# power-rail.net
KiCad netlist of a schematic drawn in EAGLE
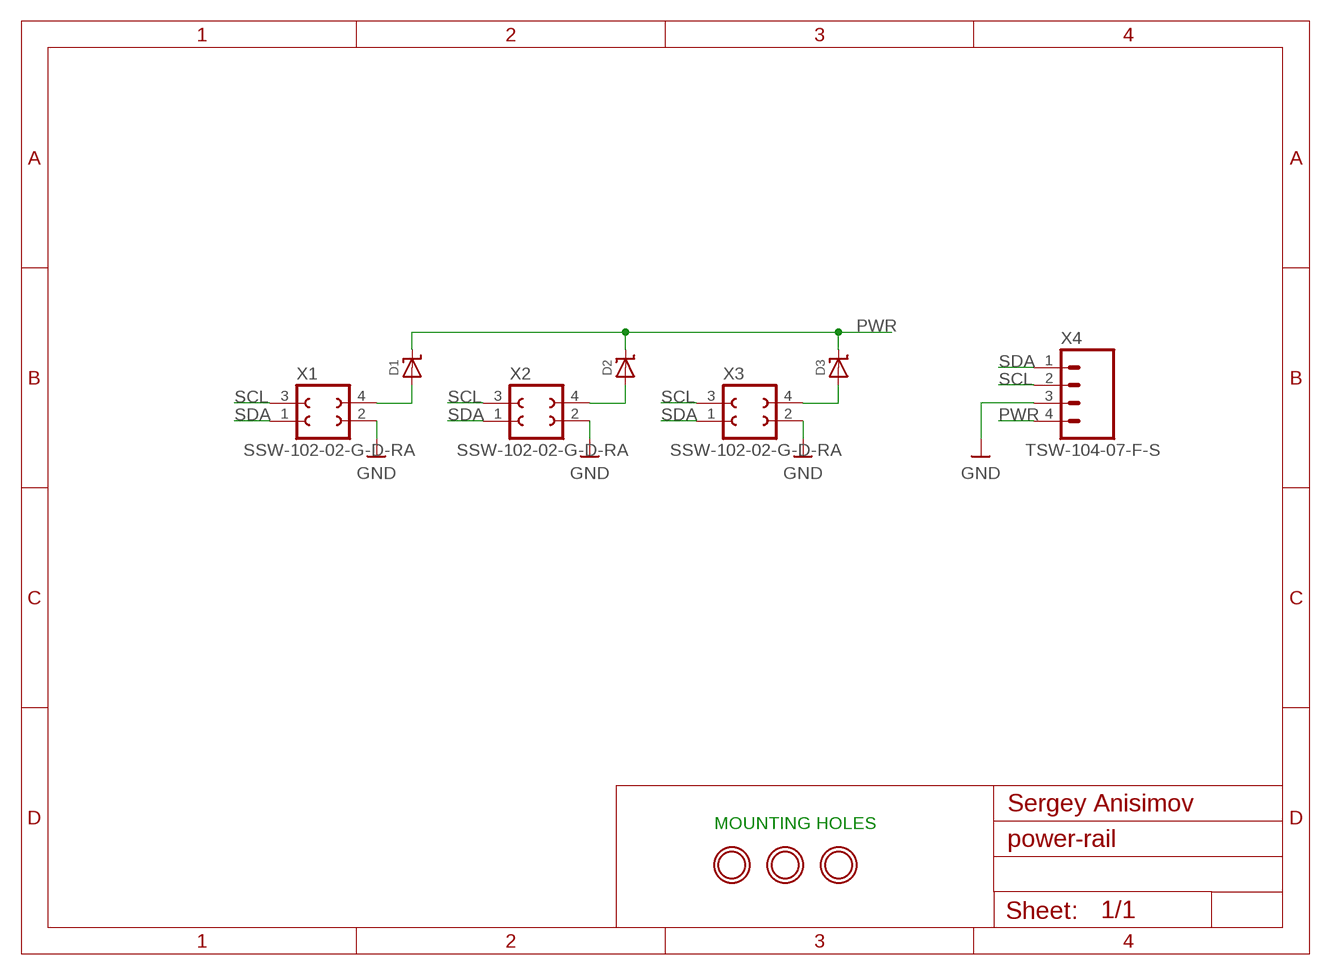
[diagram p0: schematic, sheet 1]

(export (version "E")
  (design (tool "Eeschema 10.0.6"))
  (components
    (comp (ref "D1")
      (value "DIODE-SCHOTTKYSOD−123FL")
      (footprint "eagle-import:SODFL3616X98")
      (libsource (lib "eagle-import") (part "DIODE-SCHOTTKYSOD−123FL"))
    )
    (comp (ref "D2")
      (value "DIODE-SCHOTTKYSOD−123FL")
      (footprint "eagle-import:SODFL3616X98")
      (libsource (lib "eagle-import") (part "DIODE-SCHOTTKYSOD−123FL"))
    )
    (comp (ref "D3")
      (value "DIODE-SCHOTTKYSOD−123FL")
      (footprint "eagle-import:SODFL3616X98")
      (libsource (lib "eagle-import") (part "DIODE-SCHOTTKYSOD−123FL"))
    )
    (comp (ref "U$5")
      (value "MOUNTING-HOLE2.7_THICK")
      (footprint "eagle-import:MOUNTINGHOLE_2.7_PLATED_THICK")
      (libsource (lib "eagle-import") (part "MOUNTING-HOLE2.7_THICK"))
    )
    (comp (ref "U$6")
      (value "MOUNTING-HOLE2.7_THICK")
      (footprint "eagle-import:MOUNTINGHOLE_2.7_PLATED_THICK")
      (libsource (lib "eagle-import") (part "MOUNTING-HOLE2.7_THICK"))
    )
    (comp (ref "U$7")
      (value "MOUNTING-HOLE2.7_THICK")
      (footprint "eagle-import:MOUNTINGHOLE_2.7_PLATED_THICK")
      (libsource (lib "eagle-import") (part "MOUNTING-HOLE2.7_THICK"))
    )
    (comp (ref "X1")
      (value "SSW-102-02-G-D-RA")
      (footprint "eagle-import:SSQ-102-02-T-D-RA")
      (libsource (lib "eagle-import") (part "CON-FE-02-02SSQ-102-02-T-D-RA"))
    )
    (comp (ref "X2")
      (value "SSW-102-02-G-D-RA")
      (footprint "eagle-import:SSQ-102-02-T-D-RA")
      (libsource (lib "eagle-import") (part "CON-FE-02-02SSQ-102-02-T-D-RA"))
    )
    (comp (ref "X3")
      (value "SSW-102-02-G-D-RA")
      (footprint "eagle-import:SSQ-102-02-T-D-RA")
      (libsource (lib "eagle-import") (part "CON-FE-02-02SSQ-102-02-T-D-RA"))
    )
    (comp (ref "X4")
      (value "TSW-104-07-F-S")
      (footprint "eagle-import:HDRV4W64P254_1X4_1016X254X838B")
      (libsource (lib "eagle-import") (part "CON-MA-04-01TSW-104-07-G-S"))
    )
  )
  (nets
    (net (code "1") (name "/PWR") (class "Default")
      (node (ref "D1") (pin "C") (pinfunction "C_C") (pintype "passive"))
      (node (ref "D2") (pin "C") (pinfunction "C_C") (pintype "passive"))
      (node (ref "D3") (pin "C") (pinfunction "C_C") (pintype "passive"))
      (node (ref "X4") (pin "4") (pinfunction "4_4") (pintype "passive"))
    )
    (net (code "2") (name "/SCL") (class "Default")
      (node (ref "X1") (pin "3") (pinfunction "3_3") (pintype "passive"))
      (node (ref "X2") (pin "3") (pinfunction "3_3") (pintype "passive"))
      (node (ref "X3") (pin "3") (pinfunction "3_3") (pintype "passive"))
      (node (ref "X4") (pin "2") (pinfunction "2_2") (pintype "passive"))
    )
    (net (code "3") (name "/SDA") (class "Default")
      (node (ref "X1") (pin "1") (pinfunction "1_1") (pintype "passive"))
      (node (ref "X2") (pin "1") (pinfunction "1_1") (pintype "passive"))
      (node (ref "X3") (pin "1") (pinfunction "1_1") (pintype "passive"))
      (node (ref "X4") (pin "1") (pinfunction "1_1") (pintype "passive"))
    )
    (net (code "4") (name "GND") (class "Default")
      (node (ref "X1") (pin "2") (pinfunction "2_2") (pintype "passive"))
      (node (ref "X2") (pin "2") (pinfunction "2_2") (pintype "passive"))
      (node (ref "X3") (pin "2") (pinfunction "2_2") (pintype "passive"))
      (node (ref "X4") (pin "3") (pinfunction "3_3") (pintype "passive"))
    )
    (net (code "5") (name "Net-(D1-PadA)") (class "Default")
      (node (ref "D1") (pin "A") (pinfunction "A_A") (pintype "passive"))
      (node (ref "X1") (pin "4") (pinfunction "4_4") (pintype "passive"))
    )
    (net (code "6") (name "Net-(D2-PadA)") (class "Default")
      (node (ref "D2") (pin "A") (pinfunction "A_A") (pintype "passive"))
      (node (ref "X2") (pin "4") (pinfunction "4_4") (pintype "passive"))
    )
    (net (code "7") (name "Net-(D3-PadA)") (class "Default")
      (node (ref "D3") (pin "A") (pinfunction "A_A") (pintype "passive"))
      (node (ref "X3") (pin "4") (pinfunction "4_4") (pintype "passive"))
    )
  )
)
